# AdapterQFP48forZIF.net
KiCad netlist of a schematic drawn in EAGLE
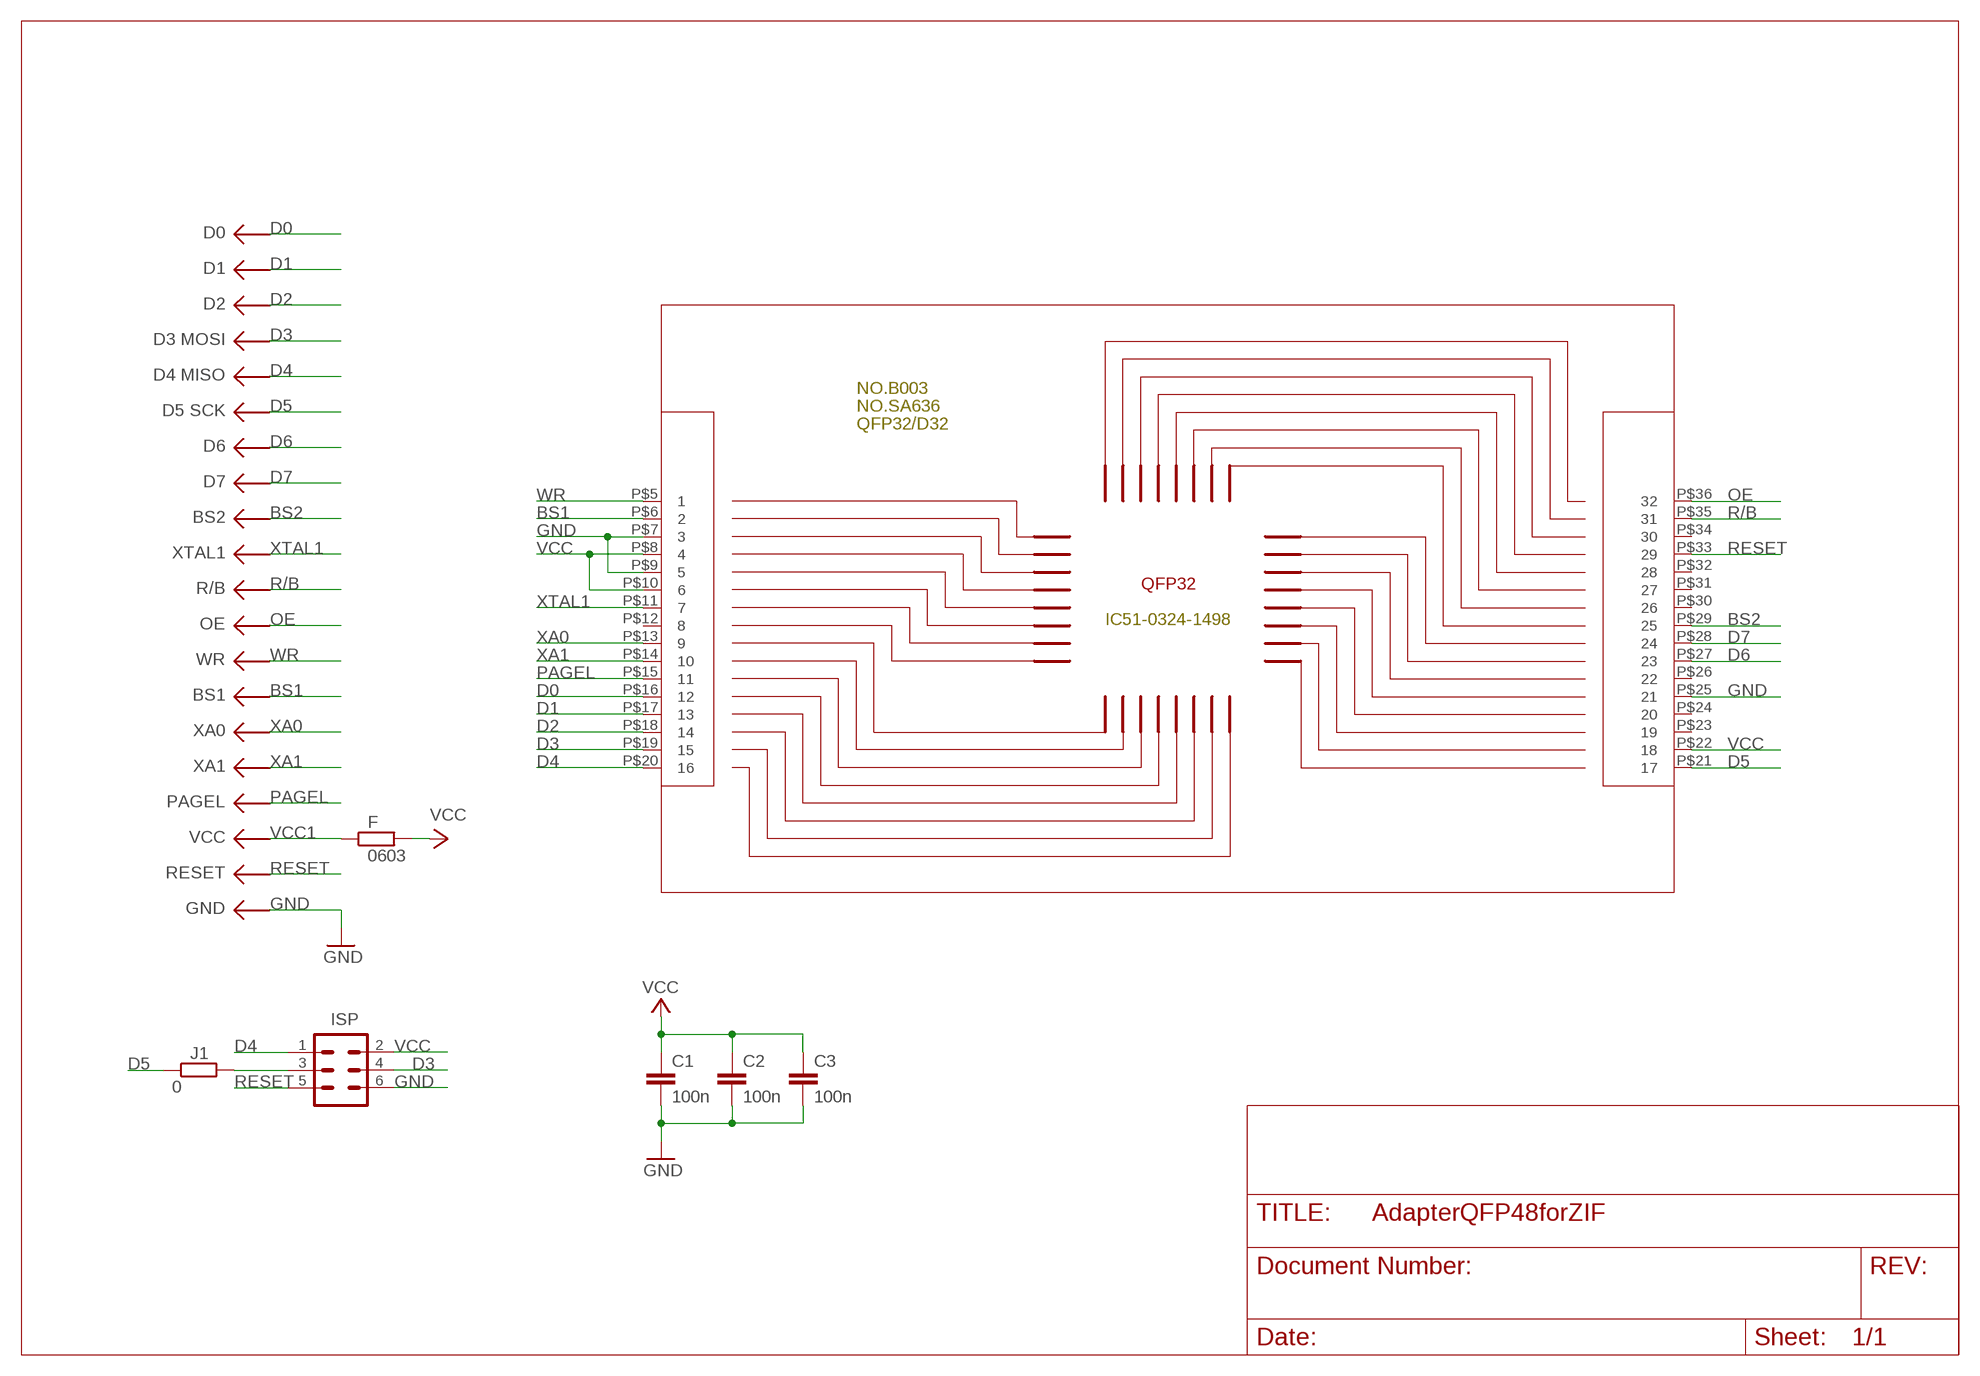
[diagram p0: schematic, sheet 1]

(export (version "E")
  (design (tool "Eeschema 10.0.6"))
  (components
    (comp (ref "C1")
      (value "100n")
      (footprint "eagle-import:RCL_C0805")
      (libsource (lib "eagle-import") (part "RCL_C-EUC0805"))
    )
    (comp (ref "C2")
      (value "100n")
      (footprint "eagle-import:RCL_C0805")
      (libsource (lib "eagle-import") (part "RCL_C-EUC0805"))
    )
    (comp (ref "C3")
      (value "100n")
      (footprint "eagle-import:RCL_C0805")
      (libsource (lib "eagle-import") (part "RCL_C-EUC0805"))
    )
    (comp (ref "F")
      (value "0603")
      (footprint "eagle-import:RCL_M0805")
      (libsource (lib "eagle-import") (part "RCL_R-EU_M0805"))
    )
    (comp (ref "ISP")
      (value "MA03-2")
      (footprint "eagle-import:MA03-2")
      (libsource (lib "eagle-import") (part "MA03-2"))
    )
    (comp (ref "J1")
      (value "0")
      (footprint "eagle-import:R1206W")
      (libsource (lib "eagle-import") (part "R-EU_R1206W"))
    )
    (comp (ref "U$1")
      (value "PROGRAMMER_P_AVR")
      (footprint "eagle-import:PROGRAMMER_P_AVR")
      (libsource (lib "eagle-import") (part "PROGRAMMER_P_AVR"))
    )
    (comp (ref "U$14")
      (value "SA636-40")
      (footprint "eagle-import:ADAPTERQFP48FORZIF")
      (libsource (lib "eagle-import") (part "SA636-40"))
    )
  )
  (nets
    (net (code "1") (name "/BS1") (class "Default")
      (node (ref "U$1") (pin "BS1") (pinfunction "BS1_BS1") (pintype "bidirectional"))
      (node (ref "U$14") (pin "P$6") (pinfunction "2_P$6") (pintype "bidirectional"))
    )
    (net (code "2") (name "/BS2") (class "Default")
      (node (ref "U$1") (pin "BS2") (pinfunction "BS2_BS2") (pintype "bidirectional"))
      (node (ref "U$14") (pin "P$29") (pinfunction "25_P$29") (pintype "bidirectional"))
    )
    (net (code "3") (name "/D0") (class "Default")
      (node (ref "U$1") (pin "D0") (pinfunction "D0_D0") (pintype "bidirectional"))
      (node (ref "U$14") (pin "P$16") (pinfunction "12_P$16") (pintype "bidirectional"))
    )
    (net (code "4") (name "/D1") (class "Default")
      (node (ref "U$1") (pin "D1") (pinfunction "D1_D1") (pintype "bidirectional"))
      (node (ref "U$14") (pin "P$17") (pinfunction "13_P$17") (pintype "bidirectional"))
    )
    (net (code "5") (name "/D2") (class "Default")
      (node (ref "U$1") (pin "D2") (pinfunction "D2_D2") (pintype "bidirectional"))
      (node (ref "U$14") (pin "P$18") (pinfunction "14_P$18") (pintype "bidirectional"))
    )
    (net (code "6") (name "/D3") (class "Default")
      (node (ref "ISP") (pin "4") (pinfunction "4_4") (pintype "passive"))
      (node (ref "U$1") (pin "D3") (pinfunction "D3_D3") (pintype "bidirectional"))
      (node (ref "U$14") (pin "P$19") (pinfunction "15_P$19") (pintype "bidirectional"))
    )
    (net (code "7") (name "/D4") (class "Default")
      (node (ref "ISP") (pin "1") (pinfunction "1_1") (pintype "passive"))
      (node (ref "U$1") (pin "D4") (pinfunction "D4_D4") (pintype "bidirectional"))
      (node (ref "U$14") (pin "P$20") (pinfunction "16_P$20") (pintype "bidirectional"))
    )
    (net (code "8") (name "/D5") (class "Default")
      (node (ref "J1") (pin "1") (pinfunction "1_1") (pintype "passive"))
      (node (ref "U$1") (pin "D5") (pinfunction "D5_D5") (pintype "bidirectional"))
      (node (ref "U$14") (pin "P$21") (pinfunction "17_P$21") (pintype "bidirectional"))
    )
    (net (code "9") (name "/D6") (class "Default")
      (node (ref "U$1") (pin "D6") (pinfunction "D6_D6") (pintype "bidirectional"))
      (node (ref "U$14") (pin "P$27") (pinfunction "23_P$27") (pintype "bidirectional"))
    )
    (net (code "10") (name "/D7") (class "Default")
      (node (ref "U$1") (pin "D7") (pinfunction "D7_D7") (pintype "bidirectional"))
      (node (ref "U$14") (pin "P$28") (pinfunction "24_P$28") (pintype "bidirectional"))
    )
    (net (code "11") (name "/OE") (class "Default")
      (node (ref "U$1") (pin "OE") (pinfunction "OE_OE") (pintype "bidirectional"))
      (node (ref "U$14") (pin "P$36") (pinfunction "32_P$36") (pintype "bidirectional"))
    )
    (net (code "12") (name "/PAGEL") (class "Default")
      (node (ref "U$1") (pin "PAGEL") (pinfunction "PAGEL_PAGEL") (pintype "bidirectional"))
      (node (ref "U$14") (pin "P$15") (pinfunction "11_P$15") (pintype "bidirectional"))
    )
    (net (code "13") (name "/RESET") (class "Default")
      (node (ref "ISP") (pin "5") (pinfunction "5_5") (pintype "passive"))
      (node (ref "U$1") (pin "RESET") (pinfunction "RESET_RESET") (pintype "bidirectional"))
      (node (ref "U$14") (pin "P$33") (pinfunction "29_P$33") (pintype "bidirectional"))
    )
    (net (code "14") (name "/R{slash}B") (class "Default")
      (node (ref "U$1") (pin "RB") (pinfunction "RB_RB") (pintype "bidirectional"))
      (node (ref "U$14") (pin "P$35") (pinfunction "31_P$35") (pintype "bidirectional"))
    )
    (net (code "15") (name "/VCC1") (class "Default")
      (node (ref "F") (pin "1") (pinfunction "1_1") (pintype "passive"))
      (node (ref "U$1") (pin "VCC") (pinfunction "VCC_VCC") (pintype "bidirectional"))
    )
    (net (code "16") (name "/WR") (class "Default")
      (node (ref "U$1") (pin "WR") (pinfunction "WR_WR") (pintype "bidirectional"))
      (node (ref "U$14") (pin "P$5") (pinfunction "1_P$5") (pintype "bidirectional"))
    )
    (net (code "17") (name "/XA0") (class "Default")
      (node (ref "U$1") (pin "XA0") (pinfunction "XA0_XA0") (pintype "bidirectional"))
      (node (ref "U$14") (pin "P$13") (pinfunction "9_P$13") (pintype "bidirectional"))
    )
    (net (code "18") (name "/XA1") (class "Default")
      (node (ref "U$1") (pin "XA1") (pinfunction "XA1_XA1") (pintype "bidirectional"))
      (node (ref "U$14") (pin "P$14") (pinfunction "10_P$14") (pintype "bidirectional"))
    )
    (net (code "19") (name "/XTAL1") (class "Default")
      (node (ref "U$1") (pin "XTAL1") (pinfunction "XTAL1_XTAL1") (pintype "bidirectional"))
      (node (ref "U$14") (pin "P$11") (pinfunction "7_P$11") (pintype "bidirectional"))
    )
    (net (code "20") (name "GND") (class "Default")
      (node (ref "C1") (pin "2") (pinfunction "2_2") (pintype "passive"))
      (node (ref "C2") (pin "2") (pinfunction "2_2") (pintype "passive"))
      (node (ref "C3") (pin "2") (pinfunction "2_2") (pintype "passive"))
      (node (ref "ISP") (pin "6") (pinfunction "6_6") (pintype "passive"))
      (node (ref "U$1") (pin "GND") (pinfunction "GND_GND") (pintype "bidirectional"))
      (node (ref "U$1") (pin "GND01") (pinfunction "GND_GND01") (pintype "bidirectional"))
      (node (ref "U$1") (pin "GND03") (pinfunction "GND_GND03") (pintype "bidirectional"))
      (node (ref "U$1") (pin "GND04") (pinfunction "GND_GND04") (pintype "bidirectional"))
      (node (ref "U$1") (pin "GND05") (pinfunction "GND_GND05") (pintype "bidirectional"))
      (node (ref "U$1") (pin "GND06") (pinfunction "GND_GND06") (pintype "bidirectional"))
      (node (ref "U$1") (pin "GND07") (pinfunction "GND_GND07") (pintype "bidirectional"))
      (node (ref "U$1") (pin "GND08") (pinfunction "GND_GND08") (pintype "bidirectional"))
      (node (ref "U$1") (pin "GND09") (pinfunction "GND_GND09") (pintype "bidirectional"))
      (node (ref "U$1") (pin "GND10") (pinfunction "GND_GND10") (pintype "bidirectional"))
      (node (ref "U$1") (pin "GND11") (pinfunction "GND_GND11") (pintype "bidirectional"))
      (node (ref "U$1") (pin "GND12") (pinfunction "GND_GND12") (pintype "bidirectional"))
      (node (ref "U$1") (pin "GND13") (pinfunction "GND_GND13") (pintype "bidirectional"))
      (node (ref "U$1") (pin "GND14") (pinfunction "GND_GND14") (pintype "bidirectional"))
      (node (ref "U$1") (pin "GND15") (pinfunction "GND_GND15") (pintype "bidirectional"))
      (node (ref "U$1") (pin "GND16") (pinfunction "GND_GND16") (pintype "bidirectional"))
      (node (ref "U$1") (pin "GND17") (pinfunction "GND_GND17") (pintype "bidirectional"))
      (node (ref "U$1") (pin "GND18") (pinfunction "GND_GND18") (pintype "bidirectional"))
      (node (ref "U$1") (pin "GND19") (pinfunction "GND_GND19") (pintype "bidirectional"))
      (node (ref "U$1") (pin "GND2") (pinfunction "GND_GND2") (pintype "bidirectional"))
      (node (ref "U$1") (pin "GND20") (pinfunction "GND_GND20") (pintype "bidirectional"))
      (node (ref "U$1") (pin "GND21") (pinfunction "GND_GND21") (pintype "bidirectional"))
      (node (ref "U$1") (pin "GND22") (pinfunction "GND_GND22") (pintype "bidirectional"))
      (node (ref "U$14") (pin "P$25") (pinfunction "21_P$25") (pintype "bidirectional"))
      (node (ref "U$14") (pin "P$7") (pinfunction "3_P$7") (pintype "bidirectional"))
      (node (ref "U$14") (pin "P$9") (pinfunction "5_P$9") (pintype "bidirectional"))
    )
    (net (code "21") (name "Net-(ISP-Pad3)") (class "Default")
      (node (ref "ISP") (pin "3") (pinfunction "3_3") (pintype "passive"))
      (node (ref "J1") (pin "2") (pinfunction "2_2") (pintype "passive"))
    )
    (net (code "22") (name "VCC") (class "Default")
      (node (ref "C1") (pin "1") (pinfunction "1_1") (pintype "passive"))
      (node (ref "C2") (pin "1") (pinfunction "1_1") (pintype "passive"))
      (node (ref "C3") (pin "1") (pinfunction "1_1") (pintype "passive"))
      (node (ref "F") (pin "2") (pinfunction "2_2") (pintype "passive"))
      (node (ref "ISP") (pin "2") (pinfunction "2_2") (pintype "passive"))
      (node (ref "U$14") (pin "P$10") (pinfunction "6_P$10") (pintype "bidirectional"))
      (node (ref "U$14") (pin "P$22") (pinfunction "18_P$22") (pintype "bidirectional"))
      (node (ref "U$14") (pin "P$8") (pinfunction "4_P$8") (pintype "bidirectional"))
    )
    (net (code "23") (name "unconnected-(U$14-8-PadP$12)") (class "Default")
      (node (ref "U$14") (pin "P$12") (pinfunction "8_P$12") (pintype "bidirectional"))
    )
    (net (code "24") (name "unconnected-(U$14-19-PadP$23)") (class "Default")
      (node (ref "U$14") (pin "P$23") (pinfunction "19_P$23") (pintype "bidirectional"))
    )
    (net (code "25") (name "unconnected-(U$14-20-PadP$24)") (class "Default")
      (node (ref "U$14") (pin "P$24") (pinfunction "20_P$24") (pintype "bidirectional"))
    )
    (net (code "26") (name "unconnected-(U$14-22-PadP$26)") (class "Default")
      (node (ref "U$14") (pin "P$26") (pinfunction "22_P$26") (pintype "bidirectional"))
    )
    (net (code "27") (name "unconnected-(U$14-26-PadP$30)") (class "Default")
      (node (ref "U$14") (pin "P$30") (pinfunction "26_P$30") (pintype "bidirectional"))
    )
    (net (code "28") (name "unconnected-(U$14-27-PadP$31)") (class "Default")
      (node (ref "U$14") (pin "P$31") (pinfunction "27_P$31") (pintype "bidirectional"))
    )
    (net (code "29") (name "unconnected-(U$14-28-PadP$32)") (class "Default")
      (node (ref "U$14") (pin "P$32") (pinfunction "28_P$32") (pintype "bidirectional"))
    )
    (net (code "30") (name "unconnected-(U$14-30-PadP$34)") (class "Default")
      (node (ref "U$14") (pin "P$34") (pinfunction "30_P$34") (pintype "bidirectional"))
    )
  )
)
